# CON_MINI_USBB_RA.net
KiCad netlist of a schematic drawn in Altium Designer
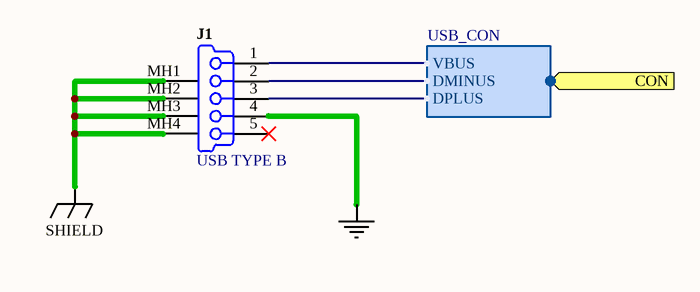
[diagram p0: CON_MINI_USBB_RA.SchDoc]

(export (version "E")
  (design (tool "Eeschema 10.0.6"))
  (components
    (comp (ref "J1")
      (value "USB TYPE B")
      (footprint "USB-MOLEX-675031020")
      (description "USB, SMD, Type B, Molex")
      (libsource (lib "AltiumDesignLibrary") (part "0481900001"))
    )
  )
  (nets
    (net (code "2") (name "/DMINUS") (class "Default")
      (node (ref "J1") (pin "2") (pinfunction "2_2") (pintype "passive"))
    )
    (net (code "3") (name "/DPLUS") (class "Default")
      (node (ref "J1") (pin "3") (pinfunction "3_3") (pintype "passive"))
    )
    (net (code "4") (name "/VBUS") (class "Default")
      (node (ref "J1") (pin "1") (pinfunction "1_1") (pintype "passive"))
    )
    (net (code "6") (name "GND") (class "Default")
      (node (ref "J1") (pin "4") (pinfunction "4_4") (pintype "passive"))
    )
    (net (code "7") (name "SHIELD") (class "Default")
      (node (ref "J1") (pin "MH1") (pinfunction "MH1_MH1") (pintype "passive"))
      (node (ref "J1") (pin "MH2") (pinfunction "MH2_MH2") (pintype "passive"))
      (node (ref "J1") (pin "MH3") (pinfunction "MH3_MH3") (pintype "passive"))
      (node (ref "J1") (pin "MH4") (pinfunction "MH4_MH4") (pintype "passive"))
    )
    (net (code "8") (name "unconnected-(J1-Pad5)") (class "Default")
      (node (ref "J1") (pin "5") (pinfunction "5_5") (pintype "passive+no_connect"))
    )
  )
)
